# LCD_Model.net
KiCad netlist of a schematic drawn in Altium Designer
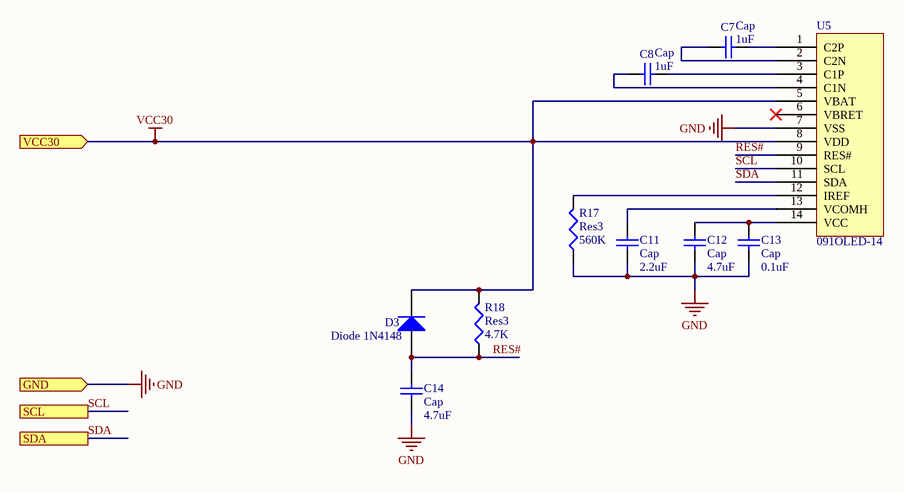
[diagram p0: LCD_Model.SchDoc]

(export (version "E")
  (design (tool "Eeschema 10.0.6"))
  (components
    (comp (ref "C7")
      (value "Cap")
      (footprint "cap-0805")
      (description "Capacitor")
      (fields (field (name "ALTIUM_VALUE") "1uF") (field (name "PUBLISHER") "Altium Limited"))
      (libsource (lib "Miscellaneous Devices") (part "Cap"))
    )
    (comp (ref "C8")
      (value "Cap")
      (footprint "cap-0805")
      (description "Capacitor")
      (fields (field (name "ALTIUM_VALUE") "1uF") (field (name "PUBLISHER") "Altium Limited"))
      (libsource (lib "Miscellaneous Devices") (part "Cap"))
    )
    (comp (ref "C11")
      (value "Cap")
      (footprint "cap-0805")
      (description "Capacitor")
      (fields (field (name "ALTIUM_VALUE") "2.2uF") (field (name "PUBLISHER") "Altium Limited"))
      (libsource (lib "Miscellaneous Devices") (part "Cap"))
    )
    (comp (ref "C12")
      (value "Cap")
      (footprint "cap-0805")
      (description "Capacitor")
      (fields (field (name "ALTIUM_VALUE") "4.7uF") (field (name "PUBLISHER") "Altium Limited"))
      (libsource (lib "Miscellaneous Devices") (part "Cap"))
    )
    (comp (ref "C13")
      (value "Cap")
      (footprint "cap-0805")
      (description "Capacitor")
      (fields (field (name "ALTIUM_VALUE") "0.1uF") (field (name "PUBLISHER") "Altium Limited"))
      (libsource (lib "Miscellaneous Devices") (part "Cap"))
    )
    (comp (ref "C14")
      (value "Cap")
      (footprint "cap-0805")
      (description "Capacitor")
      (fields (field (name "ALTIUM_VALUE") "4.7uF") (field (name "PUBLISHER") "Altium Limited"))
      (libsource (lib "Miscellaneous Devices") (part "Cap"))
    )
    (comp (ref "D3")
      (value "Diode 1N4148")
      (footprint "PQX-DIO-0805")
      (description "High Conductance Fast Diode")
      (fields (field (name "PUBLISHER") "Altium Limited"))
      (libsource (lib "Miscellaneous Devices") (part "Diode 1N4148"))
    )
    (comp (ref "R17")
      (value "Res3")
      (footprint "RES-1206")
      (description "Resistor")
      (fields (field (name "ALTIUM_VALUE") "560K") (field (name "PUBLISHER") "Altium Limited"))
      (libsource (lib "Miscellaneous Devices") (part "Res3"))
    )
    (comp (ref "R18")
      (value "Res3")
      (footprint "RES-1206")
      (description "Resistor")
      (fields (field (name "ALTIUM_VALUE") "4.7K") (field (name "PUBLISHER") "Altium Limited"))
      (libsource (lib "Miscellaneous Devices") (part "Res3"))
    )
    (comp (ref "U5")
      (value "091OLED-14")
      (footprint "091OLED-FFC/FPC-0.64")
      (libsource (lib "PqxSchlib") (part "091oled-14pin"))
    )
  )
  (nets
    (net (code "1") (name "/RES#") (class "Default")
      (node (ref "C14") (pin "2") (pinfunction "2_2") (pintype "passive"))
      (node (ref "D3") (pin "1") (pinfunction "A_1") (pintype "passive"))
      (node (ref "R18") (pin "1") (pinfunction "1_1") (pintype "passive"))
      (node (ref "U5") (pin "9") (pinfunction "RES#_9") (pintype "passive"))
    )
    (net (code "2") (name "/SCL") (class "Default")
      (node (ref "U5") (pin "10") (pinfunction "SCL_10") (pintype "passive"))
    )
    (net (code "3") (name "/SDA") (class "Default")
      (node (ref "U5") (pin "11") (pinfunction "SDA_11") (pintype "passive"))
    )
    (net (code "4") (name "GND") (class "Default")
      (node (ref "C11") (pin "2") (pinfunction "2_2") (pintype "passive"))
      (node (ref "C12") (pin "1") (pinfunction "1_1") (pintype "passive"))
      (node (ref "C13") (pin "1") (pinfunction "1_1") (pintype "passive"))
      (node (ref "C14") (pin "1") (pinfunction "1_1") (pintype "passive"))
      (node (ref "R17") (pin "1") (pinfunction "1_1") (pintype "passive"))
      (node (ref "U5") (pin "7") (pinfunction "VSS_7") (pintype "passive"))
    )
    (net (code "5") (name "Net-(U5-C1N)") (class "Default")
      (node (ref "C8") (pin "1") (pinfunction "1_1") (pintype "passive"))
      (node (ref "U5") (pin "4") (pinfunction "C1N_4") (pintype "passive"))
    )
    (net (code "6") (name "Net-(U5-C1P)") (class "Default")
      (node (ref "C8") (pin "2") (pinfunction "2_2") (pintype "passive"))
      (node (ref "U5") (pin "3") (pinfunction "C1P_3") (pintype "passive"))
    )
    (net (code "7") (name "Net-(U5-C2N)") (class "Default")
      (node (ref "C7") (pin "1") (pinfunction "1_1") (pintype "passive"))
      (node (ref "U5") (pin "2") (pinfunction "C2N_2") (pintype "passive"))
    )
    (net (code "8") (name "Net-(U5-C2P)") (class "Default")
      (node (ref "C7") (pin "2") (pinfunction "2_2") (pintype "passive"))
      (node (ref "U5") (pin "1") (pinfunction "C2P_1") (pintype "passive"))
    )
    (net (code "9") (name "Net-(U5-IREF)") (class "Default")
      (node (ref "R17") (pin "2") (pinfunction "2_2") (pintype "passive"))
      (node (ref "U5") (pin "12") (pinfunction "IREF_12") (pintype "passive"))
    )
    (net (code "10") (name "Net-(U5-VCC)") (class "Default")
      (node (ref "C12") (pin "2") (pinfunction "2_2") (pintype "passive"))
      (node (ref "C13") (pin "2") (pinfunction "2_2") (pintype "passive"))
      (node (ref "U5") (pin "14") (pinfunction "VCC_14") (pintype "passive"))
    )
    (net (code "11") (name "Net-(U5-VCOMH)") (class "Default")
      (node (ref "C11") (pin "1") (pinfunction "1_1") (pintype "passive"))
      (node (ref "U5") (pin "13") (pinfunction "VCOMH_13") (pintype "passive"))
    )
    (net (code "12") (name "VCC30") (class "Default")
      (node (ref "D3") (pin "2") (pinfunction "K_2") (pintype "passive"))
      (node (ref "R18") (pin "2") (pinfunction "2_2") (pintype "passive"))
      (node (ref "U5") (pin "5") (pinfunction "VBAT_5") (pintype "passive"))
      (node (ref "U5") (pin "8") (pinfunction "VDD_8") (pintype "passive"))
    )
    (net (code "13") (name "unconnected-(U5-VBRET-Pad6)") (class "Default")
      (node (ref "U5") (pin "6") (pinfunction "VBRET_6") (pintype "passive+no_connect"))
    )
  )
)
